# Control_Estufa.net
KiCad netlist of a schematic drawn in EAGLE
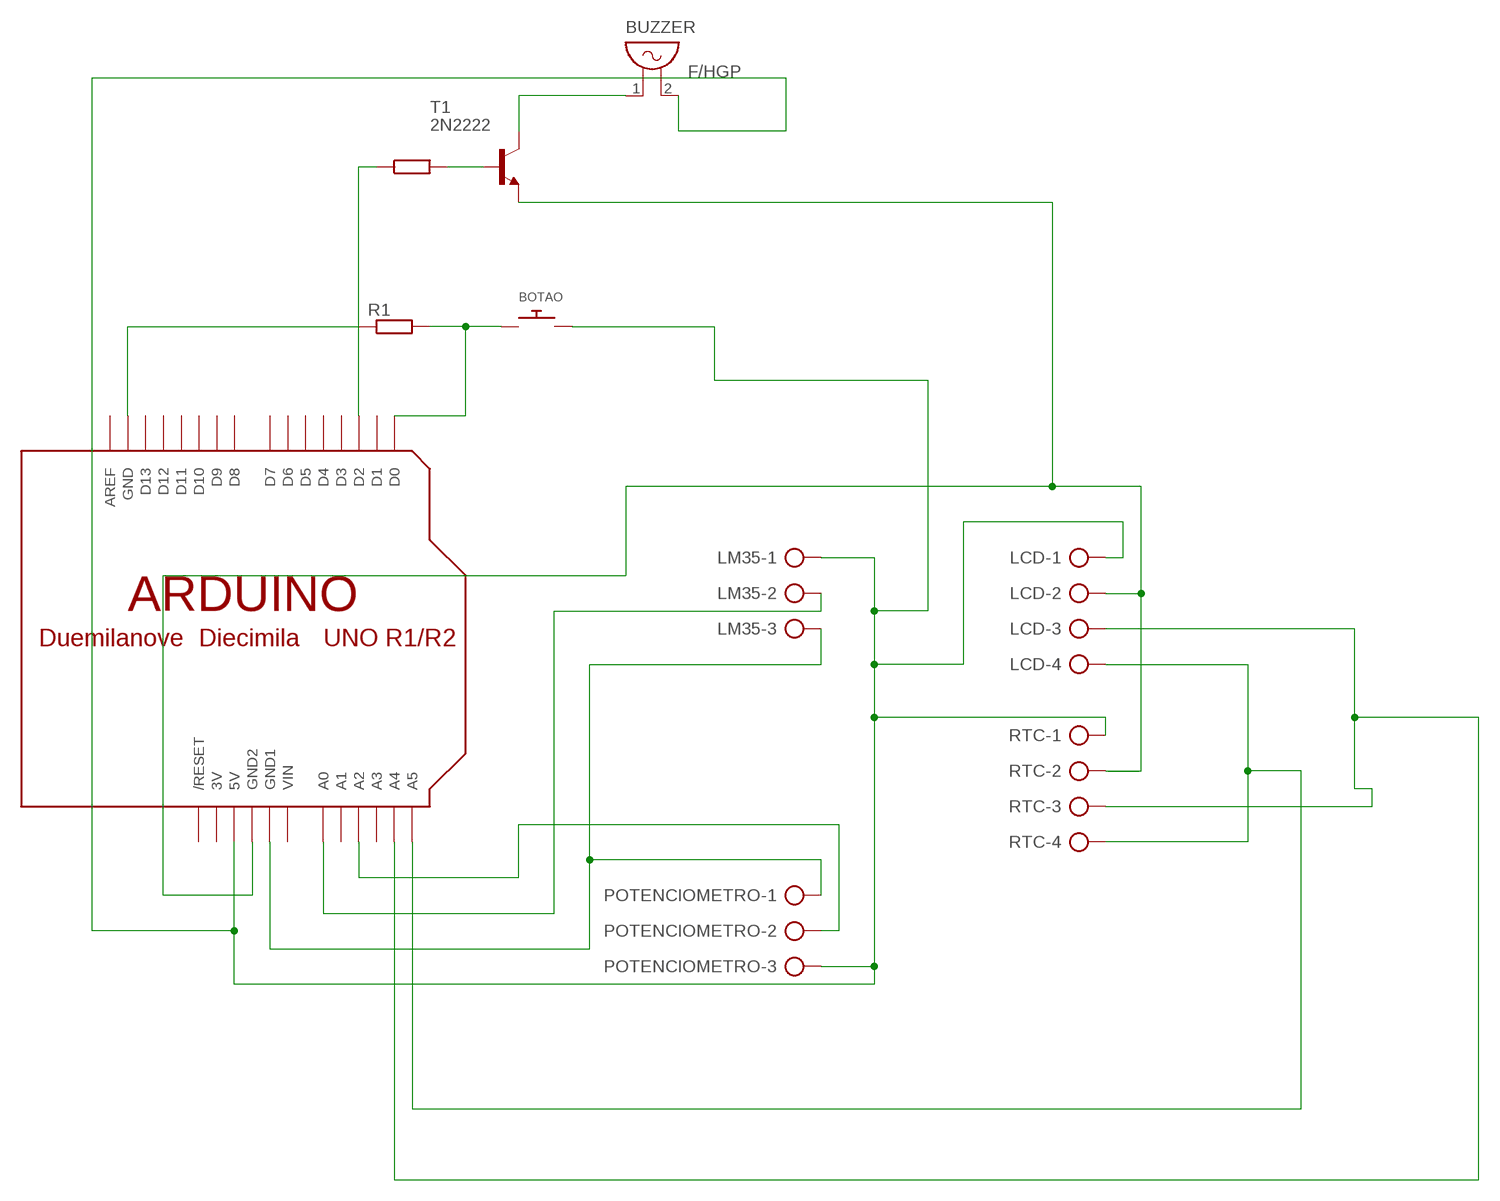
[diagram p0: schematic, sheet 1]

(export (version "E")
  (design (tool "Eeschema 10.0.6"))
  (components
    (comp (ref "BOTAO")
      (value "SWITCH_PUSHBUTTONEVQ-PE")
      (footprint "eagle-import:TACT_PANA-EVQ")
      (libsource (lib "eagle-import") (part "SWITCH_PUSHBUTTONEVQ-PE"))
    )
    (comp (ref "BUZZER")
      (value "F/HGP")
      (footprint "eagle-import:F_HGP")
      (libsource (lib "eagle-import") (part "F/HGP"))
    )
    (comp (ref "LCD")
      (value "AK500/4-H")
      (footprint "eagle-import:AK500_4-H")
      (libsource (lib "eagle-import") (part "AK500/4-H"))
    )
    (comp (ref "LM35")
      (value "AK500/3")
      (footprint "eagle-import:AK500_3")
      (libsource (lib "eagle-import") (part "AK500/3"))
    )
    (comp (ref "POTENCIOMETRO")
      (value "AK500/3")
      (footprint "eagle-import:AK500_3")
      (libsource (lib "eagle-import") (part "AK500/3"))
    )
    (comp (ref "R1")
      (value "R-EU_0207/10")
      (footprint "eagle-import:0207_10")
      (libsource (lib "eagle-import") (part "R-EU_0207/10"))
    )
    (comp (ref "RTC")
      (value "AK500/4-H")
      (footprint "eagle-import:AK500_4-H")
      (libsource (lib "eagle-import") (part "AK500/4-H"))
    )
    (comp (ref "T1")
      (value "2N2222")
      (footprint "eagle-import:TO92-EBC-OVAL")
      (libsource (lib "eagle-import") (part "2N2222"))
    )
    (comp (ref "U$1")
      (value "ARDUINO-NOHOLE")
      (footprint "eagle-import:ARDUINO-NOHOLE")
      (libsource (lib "eagle-import") (part "ARDUINO-NOHOLE"))
    )
  )
  (nets
    (net (code "1") (name "/3V") (class "Default")
      (node (ref "U$1") (pin "3V") (pinfunction "3V_3V") (pintype "power_in"))
    )
    (net (code "2") (name "/VIN") (class "Default")
      (node (ref "U$1") (pin "VIN") (pinfunction "VIN_VIN") (pintype "power_in"))
    )
    (net (code "3") (name "Net-(BOTAO-PadP$1)") (class "Default")
      (node (ref "BOTAO") (pin "P$1") (pinfunction "P$1_P$1") (pintype "passive"))
      (node (ref "R1") (pin "2") (pinfunction "2_2") (pintype "passive"))
      (node (ref "U$1") (pin "D0") (pinfunction "D0_D0") (pintype "bidirectional"))
    )
    (net (code "4") (name "Net-(BUZZER-Pad1)") (class "Default")
      (node (ref "BUZZER") (pin "1") (pinfunction "1_1") (pintype "passive"))
      (node (ref "T1") (pin "C") (pinfunction "C_C") (pintype "passive"))
    )
    (net (code "5") (name "Net-(LCDA-KL)") (class "Default")
      (node (ref "BOTAO") (pin "P$2") (pinfunction "P$2_P$2") (pintype "passive"))
      (node (ref "BUZZER") (pin "2") (pinfunction "2_2") (pintype "passive"))
      (node (ref "LCD") (pin "1") (pinfunction "KL_1") (pintype "passive"))
      (node (ref "LM35") (pin "1") (pinfunction "KL_1") (pintype "passive"))
      (node (ref "POTENCIOMETRO") (pin "3") (pinfunction "KL_3") (pintype "passive"))
      (node (ref "RTC") (pin "1") (pinfunction "KL_1") (pintype "passive"))
      (node (ref "U$1") (pin "5V") (pinfunction "5V_5V") (pintype "power_in"))
    )
    (net (code "6") (name "Net-(LCDB-KL)") (class "Default")
      (node (ref "LCD") (pin "2") (pinfunction "KL_2") (pintype "passive"))
      (node (ref "RTC") (pin "2") (pinfunction "KL_2") (pintype "passive"))
      (node (ref "T1") (pin "E") (pinfunction "E_E") (pintype "passive"))
      (node (ref "U$1") (pin "GND2") (pinfunction "GND2_GND2") (pintype "power_in"))
    )
    (net (code "7") (name "Net-(LCDC-KL)") (class "Default")
      (node (ref "LCD") (pin "3") (pinfunction "KL_3") (pintype "passive"))
      (node (ref "RTC") (pin "3") (pinfunction "KL_3") (pintype "passive"))
      (node (ref "U$1") (pin "A4") (pinfunction "A4_A4") (pintype "bidirectional"))
    )
    (net (code "8") (name "Net-(LCDD-KL)") (class "Default")
      (node (ref "LCD") (pin "4") (pinfunction "KL_4") (pintype "passive"))
      (node (ref "RTC") (pin "4") (pinfunction "KL_4") (pintype "passive"))
      (node (ref "U$1") (pin "A5") (pinfunction "A5_A5") (pintype "bidirectional"))
    )
    (net (code "9") (name "Net-(LM35B-KL)") (class "Default")
      (node (ref "LM35") (pin "2") (pinfunction "KL_2") (pintype "passive"))
      (node (ref "U$1") (pin "A0") (pinfunction "A0_A0") (pintype "bidirectional"))
    )
    (net (code "10") (name "Net-(LM35C-KL)") (class "Default")
      (node (ref "LM35") (pin "3") (pinfunction "KL_3") (pintype "passive"))
      (node (ref "POTENCIOMETRO") (pin "1") (pinfunction "KL_1") (pintype "passive"))
      (node (ref "U$1") (pin "GND1") (pinfunction "GND1_GND1") (pintype "power_in"))
    )
    (net (code "11") (name "Net-(POTENCIOMETROB-KL)") (class "Default")
      (node (ref "POTENCIOMETRO") (pin "2") (pinfunction "KL_2") (pintype "passive"))
      (node (ref "U$1") (pin "A2") (pinfunction "A2_A2") (pintype "bidirectional"))
    )
    (net (code "12") (name "Net-(R1-Pad1)") (class "Default")
      (node (ref "R1") (pin "1") (pinfunction "1_1") (pintype "passive"))
      (node (ref "U$1") (pin "GND") (pinfunction "GND_GND") (pintype "power_in"))
    )
    (net (code "13") (name "unconnected-(T1-PadB)") (class "Default")
      (node (ref "T1") (pin "B") (pinfunction "B_B") (pintype "passive"))
    )
    (net (code "14") (name "unconnected-(U$1-PadA1)") (class "Default")
      (node (ref "U$1") (pin "A1") (pinfunction "A1_A1") (pintype "bidirectional"))
    )
    (net (code "15") (name "unconnected-(U$1-PadA3)") (class "Default")
      (node (ref "U$1") (pin "A3") (pinfunction "A3_A3") (pintype "bidirectional"))
    )
    (net (code "16") (name "unconnected-(U$1-PadAREF)") (class "Default")
      (node (ref "U$1") (pin "AREF") (pinfunction "AREF_AREF") (pintype "bidirectional"))
    )
    (net (code "17") (name "unconnected-(U$1-PadD1)") (class "Default")
      (node (ref "U$1") (pin "D1") (pinfunction "D1_D1") (pintype "bidirectional"))
    )
    (net (code "18") (name "unconnected-(U$1-PadD2)") (class "Default")
      (node (ref "U$1") (pin "D2") (pinfunction "D2_D2") (pintype "bidirectional"))
    )
    (net (code "19") (name "unconnected-(U$1-PadD3)") (class "Default")
      (node (ref "U$1") (pin "D3") (pinfunction "D3_D3") (pintype "bidirectional"))
    )
    (net (code "20") (name "unconnected-(U$1-PadD4)") (class "Default")
      (node (ref "U$1") (pin "D4") (pinfunction "D4_D4") (pintype "bidirectional"))
    )
    (net (code "21") (name "unconnected-(U$1-PadD5)") (class "Default")
      (node (ref "U$1") (pin "D5") (pinfunction "D5_D5") (pintype "bidirectional"))
    )
    (net (code "22") (name "unconnected-(U$1-PadD6)") (class "Default")
      (node (ref "U$1") (pin "D6") (pinfunction "D6_D6") (pintype "bidirectional"))
    )
    (net (code "23") (name "unconnected-(U$1-PadD7)") (class "Default")
      (node (ref "U$1") (pin "D7") (pinfunction "D7_D7") (pintype "bidirectional"))
    )
    (net (code "24") (name "unconnected-(U$1-PadD8)") (class "Default")
      (node (ref "U$1") (pin "D8") (pinfunction "D8_D8") (pintype "bidirectional"))
    )
    (net (code "25") (name "unconnected-(U$1-PadD9)") (class "Default")
      (node (ref "U$1") (pin "D9") (pinfunction "D9_D9") (pintype "bidirectional"))
    )
    (net (code "26") (name "unconnected-(U$1-PadD10)") (class "Default")
      (node (ref "U$1") (pin "D10") (pinfunction "D10_D10") (pintype "bidirectional"))
    )
    (net (code "27") (name "unconnected-(U$1-PadD11)") (class "Default")
      (node (ref "U$1") (pin "D11") (pinfunction "D11_D11") (pintype "bidirectional"))
    )
    (net (code "28") (name "unconnected-(U$1-PadD12)") (class "Default")
      (node (ref "U$1") (pin "D12") (pinfunction "D12_D12") (pintype "bidirectional"))
    )
    (net (code "29") (name "unconnected-(U$1-PadD13)") (class "Default")
      (node (ref "U$1") (pin "D13") (pinfunction "D13_D13") (pintype "bidirectional"))
    )
    (net (code "30") (name "unconnected-(U$1-{slash}RESET-PadRESET)") (class "Default")
      (node (ref "U$1") (pin "RESET") (pinfunction "/RESET_RESET") (pintype "bidirectional"))
    )
  )
)
